# Tiva_Xbee.net
KiCad netlist of a schematic drawn in EAGLE
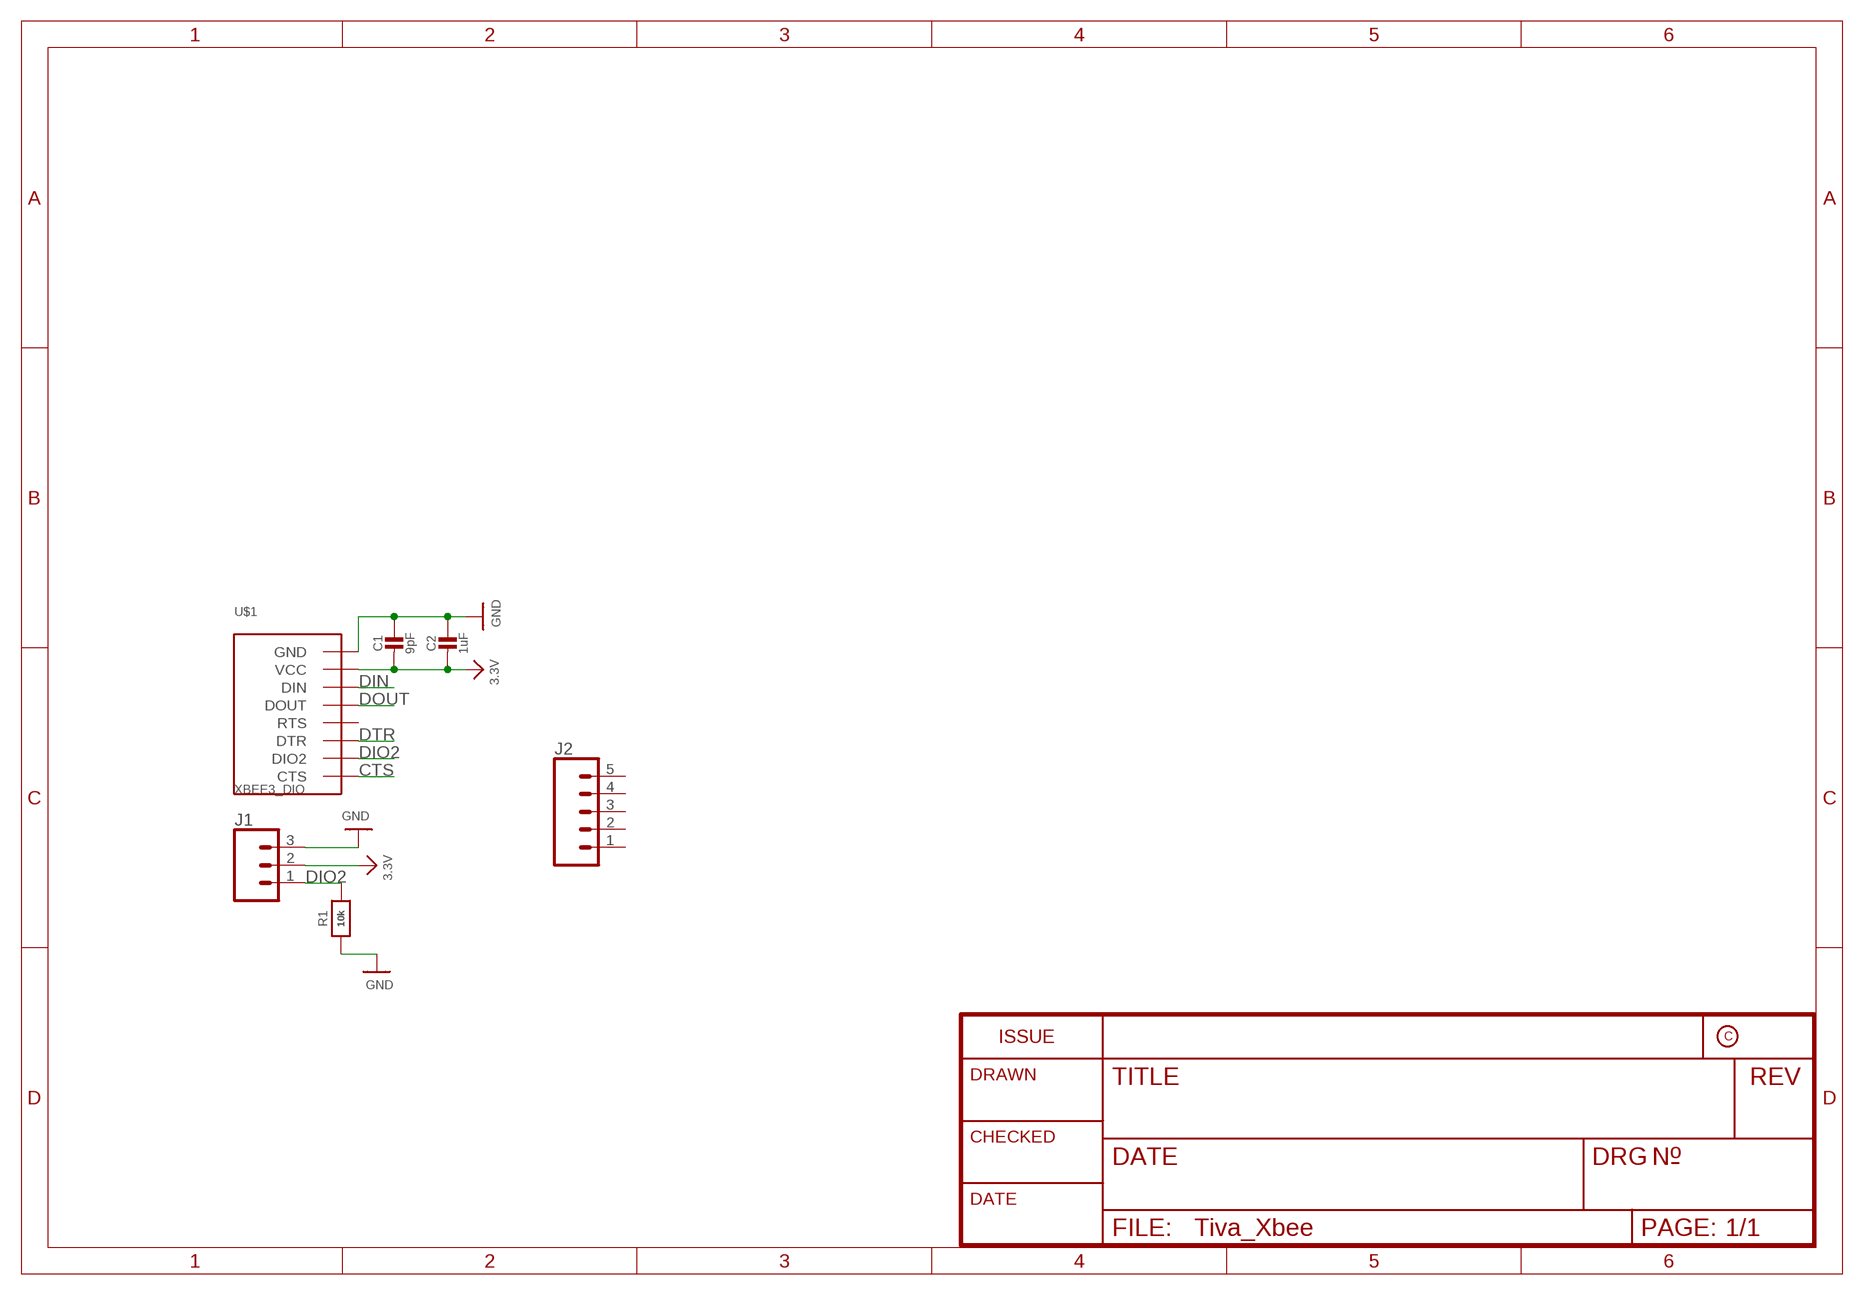
[diagram p0: schematic, sheet 1]

(export (version "E")
  (design (tool "Eeschema 10.0.6"))
  (components
    (comp (ref "C1")
      (value "9pF")
      (footprint "eagle-import:_0603")
      (libsource (lib "eagle-import") (part "CAP_CERAMIC_0603"))
    )
    (comp (ref "C2")
      (value "1uF")
      (footprint "eagle-import:_0603")
      (libsource (lib "eagle-import") (part "CAP_CERAMIC_0603"))
    )
    (comp (ref "J1")
      (value "CONN_03")
      (footprint "eagle-import:1X03")
      (libsource (lib "eagle-import") (part "CONN_03"))
    )
    (comp (ref "J2")
      (value "CONN_05")
      (footprint "eagle-import:1X05")
      (libsource (lib "eagle-import") (part "CONN_05"))
    )
    (comp (ref "R1")
      (value "10k")
      (footprint "eagle-import:_0603")
      (libsource (lib "eagle-import") (part "RESISTOR_0603"))
    )
    (comp (ref "U$1")
      (value "XBEE3_DIO")
      (footprint "eagle-import:XBEE3_MICRO")
      (libsource (lib "eagle-import") (part "XBEE3_DIO"))
    )
  )
  (nets
    (net (code "1") (name "/CTS") (class "Default")
      (node (ref "U$1") (pin "CTS/DIO7") (pinfunction "CTS_CTS/DIO7") (pintype "bidirectional"))
    )
    (net (code "2") (name "/DIN") (class "Default")
      (node (ref "U$1") (pin "DIN/CONFIG/DIO14") (pinfunction "DIN_DIN/CONFIG/DIO14") (pintype "bidirectional"))
    )
    (net (code "3") (name "/DIO2") (class "Default")
      (node (ref "J1") (pin "1") (pinfunction "1_1") (pintype "passive"))
      (node (ref "R1") (pin "2") (pinfunction "2_2") (pintype "passive"))
      (node (ref "U$1") (pin "AD2/DIO2") (pinfunction "DIO2_AD2/DIO2") (pintype "bidirectional"))
    )
    (net (code "4") (name "/DOUT") (class "Default")
      (node (ref "U$1") (pin "DOUT/DIO13") (pinfunction "DOUT_DOUT/DIO13") (pintype "bidirectional"))
    )
    (net (code "5") (name "/DTR") (class "Default")
      (node (ref "U$1") (pin "DTR/SLEEP_RQ/DIO8") (pinfunction "DTR_DTR/SLEEP_RQ/DIO8") (pintype "bidirectional"))
    )
    (net (code "6") (name "3.3V") (class "Default")
      (node (ref "C1") (pin "2") (pinfunction "2_2") (pintype "passive"))
      (node (ref "C2") (pin "2") (pinfunction "2_2") (pintype "passive"))
      (node (ref "J1") (pin "2") (pinfunction "2_2") (pintype "passive"))
      (node (ref "U$1") (pin "VCC") (pinfunction "VCC_VCC") (pintype "bidirectional"))
    )
    (net (code "7") (name "GND") (class "Default")
      (node (ref "C1") (pin "1") (pinfunction "1_1") (pintype "passive"))
      (node (ref "C2") (pin "1") (pinfunction "1_1") (pintype "passive"))
      (node (ref "J1") (pin "3") (pinfunction "3_3") (pintype "passive"))
      (node (ref "R1") (pin "1") (pinfunction "1_1") (pintype "passive"))
      (node (ref "U$1") (pin "GND1") (pinfunction "GND_GND1") (pintype "bidirectional"))
      (node (ref "U$1") (pin "GND2") (pinfunction "GND_GND2") (pintype "bidirectional"))
      (node (ref "U$1") (pin "GND3") (pinfunction "GND_GND3") (pintype "bidirectional"))
      (node (ref "U$1") (pin "GND4") (pinfunction "GND_GND4") (pintype "bidirectional"))
      (node (ref "U$1") (pin "GND5") (pinfunction "GND_GND5") (pintype "bidirectional"))
      (node (ref "U$1") (pin "GND6") (pinfunction "GND_GND6") (pintype "bidirectional"))
    )
    (net (code "8") (name "unconnected-(J2-Pad1)") (class "Default")
      (node (ref "J2") (pin "1") (pinfunction "1_1") (pintype "passive"))
    )
    (net (code "9") (name "unconnected-(J2-Pad2)") (class "Default")
      (node (ref "J2") (pin "2") (pinfunction "2_2") (pintype "passive"))
    )
    (net (code "10") (name "unconnected-(J2-Pad3)") (class "Default")
      (node (ref "J2") (pin "3") (pinfunction "3_3") (pintype "passive"))
    )
    (net (code "11") (name "unconnected-(J2-Pad4)") (class "Default")
      (node (ref "J2") (pin "4") (pinfunction "4_4") (pintype "passive"))
    )
    (net (code "12") (name "unconnected-(J2-Pad5)") (class "Default")
      (node (ref "J2") (pin "5") (pinfunction "5_5") (pintype "passive"))
    )
    (net (code "13") (name "unconnected-(U$1-RTS-PadRTS{slash}DIO6)") (class "Default")
      (node (ref "U$1") (pin "RTS/DIO6") (pinfunction "RTS_RTS/DIO6") (pintype "bidirectional"))
    )
  )
)
